# Blackfoot.net
KiCad netlist of a schematic drawn in EAGLE
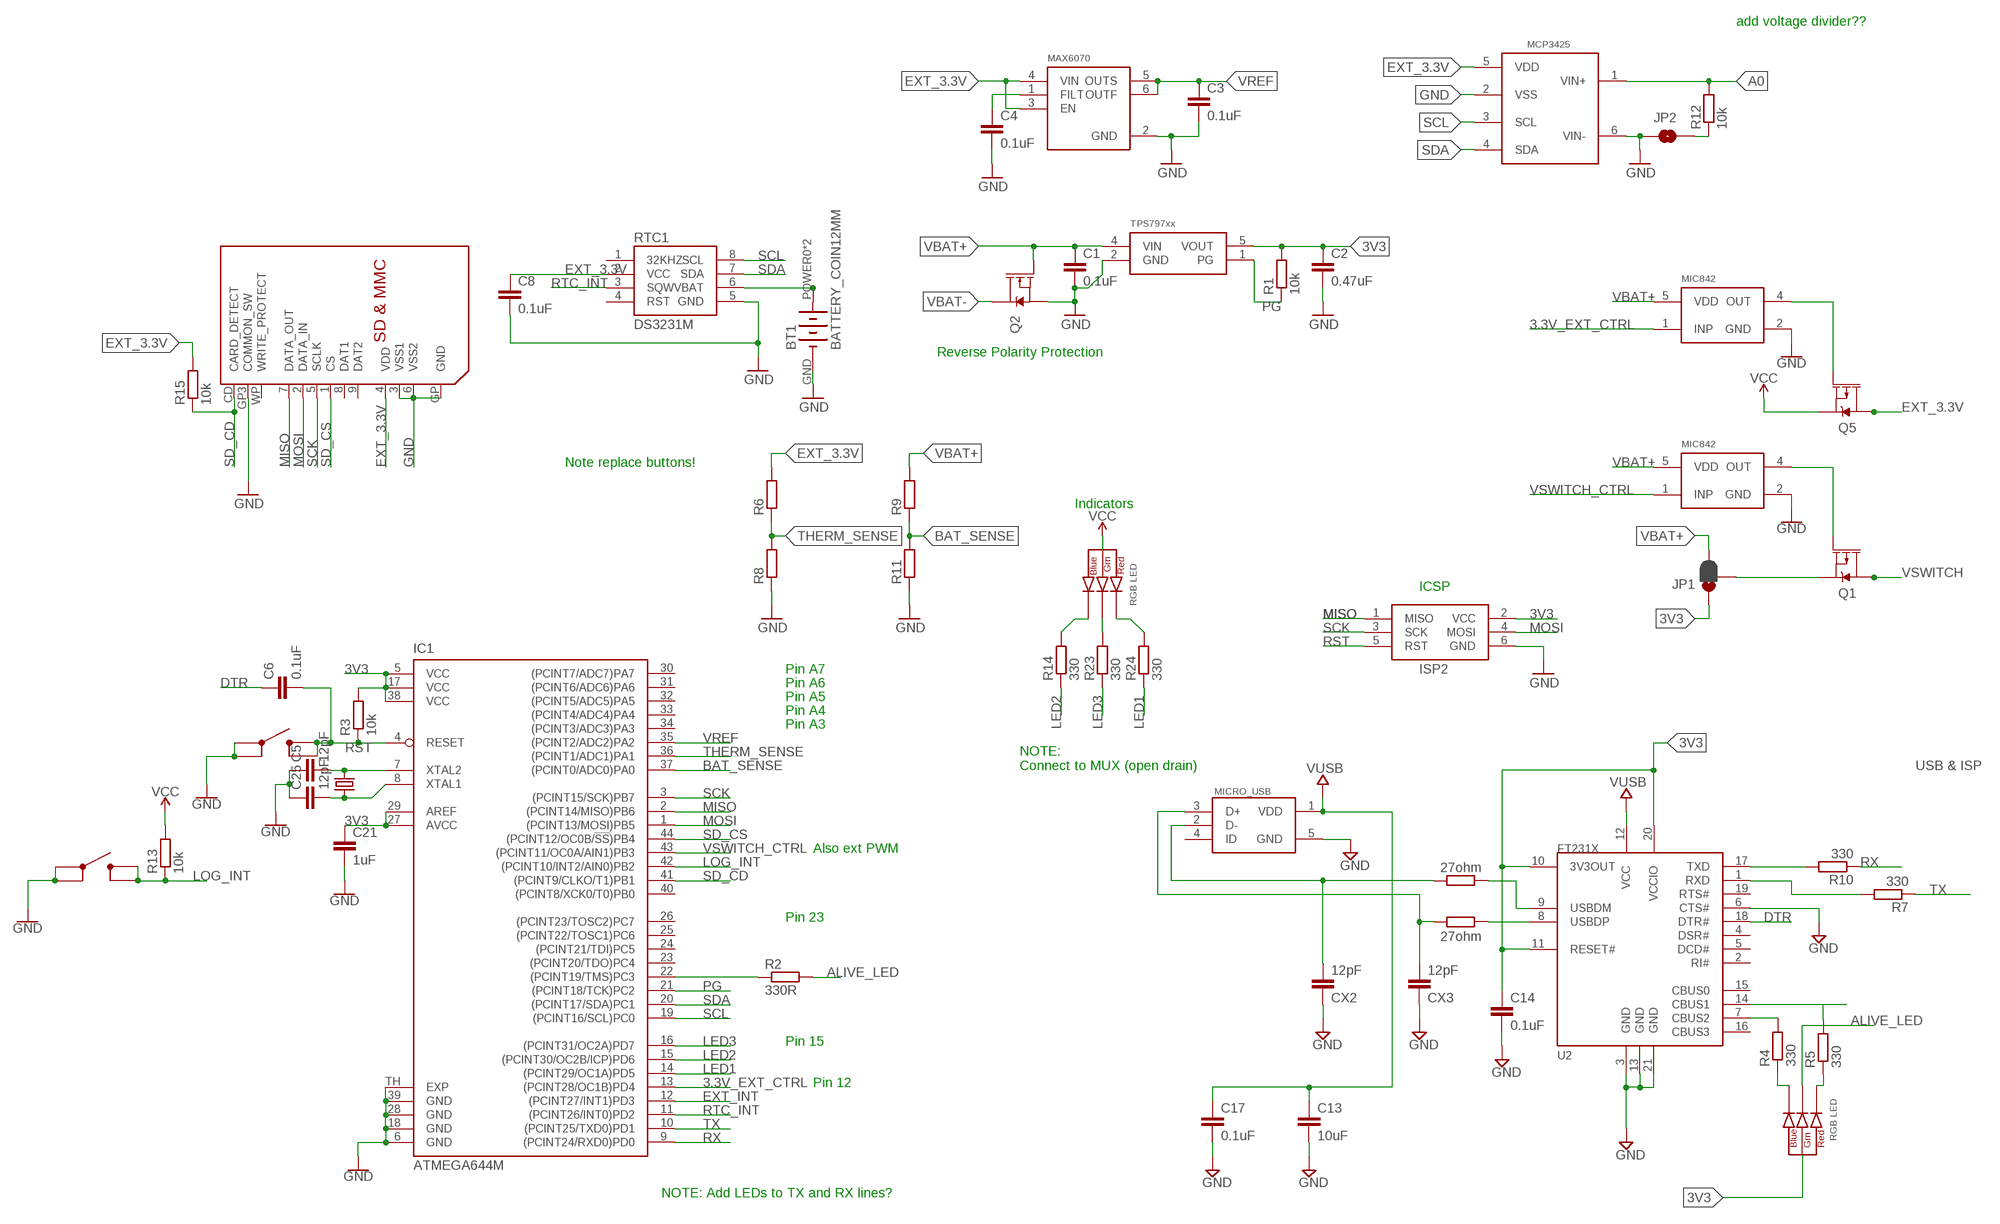
[diagram p0: schematic, sheet 1]
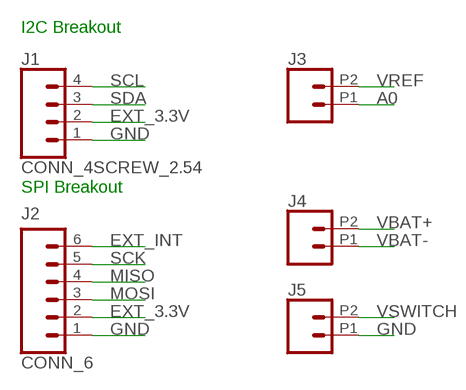
[diagram p1: schematic, sheet 2]

(export (version "E")
  (design (tool "Eeschema 10.0.6"))
  (components
    (comp (ref "J1")
      (value "CONN_4SCREW_2.54")
      (footprint "eagle-import:1X04")
      (libsource (lib "eagle-import") (part "CONN_4SCREW_2.54"))
    )
    (comp (ref "J2")
      (value "CONN_6")
      (footprint "eagle-import:1X06_SCREW")
      (libsource (lib "eagle-import") (part "CONN_6"))
    )
    (comp (ref "J3")
      (value "CONN_022.54MM_SCREWTERM")
      (footprint "eagle-import:1X02_2.54_SCREWTERM")
      (libsource (lib "eagle-import") (part "CONN_022.54MM_SCREWTERM"))
    )
    (comp (ref "J4")
      (value "CONN_022.54MM_SCREWTERM")
      (footprint "eagle-import:1X02_2.54_SCREWTERM")
      (libsource (lib "eagle-import") (part "CONN_022.54MM_SCREWTERM"))
    )
    (comp (ref "J5")
      (value "CONN_022.54MM_SCREWTERM")
      (footprint "eagle-import:1X02_2.54_SCREWTERM")
      (libsource (lib "eagle-import") (part "CONN_022.54MM_SCREWTERM"))
    )
    (comp (ref "BT1")
      (value "BATTERY_COIN12MM")
      (footprint "eagle-import:AWICKERT_LINX_BAT-HLD-012-SMT")
      (fields (field (name "MF") "Linx") (field (name "MPN") "BAT-HLD-012-SMT"))
      (libsource (lib "eagle-import") (part "BATTERY_COIN12MM"))
    )
    (comp (ref "C1")
      (value "0.1uF")
      (footprint "eagle-import:C0603")
      (libsource (lib "eagle-import") (part "bschulz_passives_C-EUC0603"))
    )
    (comp (ref "C2")
      (value "0.47uF")
      (footprint "eagle-import:C0603")
      (libsource (lib "eagle-import") (part "bschulz_passives_C-EUC0603"))
    )
    (comp (ref "C3")
      (value "0.1uF")
      (footprint "eagle-import:C0603")
      (libsource (lib "eagle-import") (part "bschulz_passives_C-EUC0603"))
    )
    (comp (ref "C4")
      (value "0.1uF")
      (footprint "eagle-import:C0603")
      (libsource (lib "eagle-import") (part "bschulz_passives_C-EUC0603"))
    )
    (comp (ref "C5")
      (value "12pF")
      (footprint "eagle-import:C0603")
      (fields
        (field (name "MF") "Samsung")
        (field (name "MPN") "CL10C120JB8NNNC")
        (field (name "DIGIKEY") "1276-1254-1-ND")
        (field (name "MF_1") "Samsung")
        (field (name "MPN_1") "CL10C120JB8NNNC")
      )
      (libsource (lib "eagle-import") (part "C-EUC060312PF"))
    )
    (comp (ref "C6")
      (value "0.1uF")
      (footprint "eagle-import:C0603")
      (fields (field (name "MF") "Samsung") (field (name "MPN") "CL10B104KO8NNNC"))
      (libsource (lib "eagle-import") (part "C-EUC06030.1UF"))
    )
    (comp (ref "C8")
      (value "0.1uF")
      (footprint "eagle-import:C0603")
      (libsource (lib "eagle-import") (part "C-EUC0603"))
    )
    (comp (ref "C13")
      (value "10uF")
      (footprint "eagle-import:C0805")
      (fields (field (name "MF") "Samsung") (field (name "MPN") "CL21A106KQCLRNC"))
      (libsource (lib "eagle-import") (part "C-EUC080510UF"))
    )
    (comp (ref "C14")
      (value "0.1uF")
      (footprint "eagle-import:C0603")
      (fields (field (name "MF") "Samsung") (field (name "MPN") "CL10B104KO8NNNC"))
      (libsource (lib "eagle-import") (part "C-EUC06030.1UF"))
    )
    (comp (ref "C17")
      (value "0.1uF")
      (footprint "eagle-import:C0603")
      (fields (field (name "MF") "Samsung") (field (name "MPN") "CL10B104KO8NNNC"))
      (libsource (lib "eagle-import") (part "C-EUC06030.1UF"))
    )
    (comp (ref "C21")
      (value "1uF")
      (footprint "eagle-import:C0603")
      (fields
        (field (name "MF") "Samsung")
        (field (name "MPN") "1276-6524-1-ND")
        (field (name "DIGIKEY") "1276-6524-1-ND")
        (field (name "MF_1") "Samsung")
        (field (name "MPN_1") "CL10B105MO8NNWC")
      )
      (libsource (lib "eagle-import") (part "C-EUC06031UF"))
    )
    (comp (ref "C25")
      (value "12pF")
      (footprint "eagle-import:C0603")
      (fields
        (field (name "MF") "Samsung")
        (field (name "MPN") "CL10C120JB8NNNC")
        (field (name "DIGIKEY") "1276-1254-1-ND")
        (field (name "MF_1") "Samsung")
        (field (name "MPN_1") "CL10C120JB8NNNC")
      )
      (libsource (lib "eagle-import") (part "C-EUC060312PF"))
    )
    (comp (ref "CX2")
      (value "12pF")
      (footprint "eagle-import:C0603")
      (fields (field (name "MF") "Samsung") (field (name "MPN") "CL10C120JB8NNNC"))
      (libsource (lib "eagle-import") (part "C-EUC060312PF"))
    )
    (comp (ref "CX3")
      (value "12pF")
      (footprint "eagle-import:C0603")
      (fields (field (name "MF") "Samsung") (field (name "MPN") "CL10C120JB8NNNC"))
      (libsource (lib "eagle-import") (part "C-EUC060312PF"))
    )
    (comp (ref "D+")
      (value "27ohm")
      (footprint "eagle-import:R0603")
      (fields
        (field (name "MF") "Yageo")
        (field (name "MPN") "RC0603FR-0727RL")
        (field (name "VALUE_PART") "27")
      )
      (libsource (lib "eagle-import") (part "R-EU_R060327"))
    )
    (comp (ref "D-")
      (value "27ohm")
      (footprint "eagle-import:R0603")
      (fields
        (field (name "MF") "Yageo")
        (field (name "MPN") "RC0603FR-0727RL")
        (field (name "VALUE_PART") "27")
      )
      (libsource (lib "eagle-import") (part "R-EU_R060327"))
    )
    (comp (ref "IC1")
      (value "ATMEGA644M")
      (footprint "eagle-import:MLF44-TH")
      (fields (field (name "MF") "Atmel") (field (name "MPN") "ATMEGA644PA-MUR"))
      (libsource (lib "eagle-import") (part "ATMEGA644M"))
    )
    (comp (ref "ISP2")
      (value "AVRISP-6")
      (footprint "eagle-import:AVRISP")
      (fields (field (name "MF") "Amphenol") (field (name "MPN") "67997-206HLF"))
      (libsource (lib "eagle-import") (part "AVRISP-6"))
    )
    (comp (ref "JP1")
      (value "JUMPER-SMT_3_1-NC_PASTE_SILK")
      (footprint "eagle-import:SMT-JUMPER_3_1-NC_PASTE_SILK")
      (libsource (lib "eagle-import") (part "JUMPER-SMT_3_1-NC_PASTE_SILK"))
    )
    (comp (ref "JP2")
      (value "JUMPER-SMT_2_NO_SILK")
      (footprint "eagle-import:SMT-JUMPER_2_NO_SILK")
      (libsource (lib "eagle-import") (part "JUMPER-SMT_2_NO_SILK"))
    )
    (comp (ref "MICRO_USB")
      (value "MICRO_USB_LONGPADS")
      (footprint "eagle-import:10118194-0001LF_10118194-0001LF_LONGER_PADS")
      (libsource (lib "eagle-import") (part "MICRO_USB_LONGPADS"))
    )
    (comp (ref "Q1")
      (value "MOSFET_PCH-IRLML2244")
      (footprint "eagle-import:SOT23-3")
      (fields (field (name "MF") "Fairchild") (field (name "MPN") "FDN360P"))
      (libsource (lib "eagle-import") (part "MOSFET_PCH-IRLML2244"))
    )
    (comp (ref "Q2")
      (value "MOSFET-NCH-DMG3404L")
      (footprint "eagle-import:SOT23-3")
      (libsource (lib "eagle-import") (part "MOSFET-NCH-DMG3404L"))
    )
    (comp (ref "Q5")
      (value "MOSFET_PCH-IRLML2244")
      (footprint "eagle-import:SOT23-3")
      (fields (field (name "MF") "Fairchild") (field (name "MPN") "FDN360P"))
      (libsource (lib "eagle-import") (part "MOSFET_PCH-IRLML2244"))
    )
    (comp (ref "R1")
      (value "10k")
      (footprint "eagle-import:R0603")
      (libsource (lib "eagle-import") (part "R-EU_R0603"))
    )
    (comp (ref "R2")
      (value "330R")
      (footprint "eagle-import:R0603")
      (libsource (lib "eagle-import") (part "R-EU_R0603"))
    )
    (comp (ref "R3")
      (value "10k")
      (footprint "eagle-import:R0603")
      (fields
        (field (name "MF") "Yageo")
        (field (name "MPN") "RC0603FR-0710KL")
        (field (name "DIGIKEY") "311-10.0KHRCT-ND")
      )
      (libsource (lib "eagle-import") (part "R-EU_R060310K"))
    )
    (comp (ref "R4")
      (value "330")
      (footprint "eagle-import:R0603")
      (fields
        (field (name "MF") "Yageo")
        (field (name "MPN") "RC0603FR-07330RL")
        (field (name "MPN_1") "RC0603FR-07330RL")
      )
      (libsource (lib "eagle-import") (part "R-EU_R0603330"))
    )
    (comp (ref "R5")
      (value "330")
      (footprint "eagle-import:R0603")
      (fields
        (field (name "MF") "Yageo")
        (field (name "MPN") "RC0603FR-07330RL")
        (field (name "DIGIKEY") "311-330HRCT-ND")
        (field (name "MF_1") "Yageo")
        (field (name "MPN_1") "RC0603FR-07330RL")
      )
      (libsource (lib "eagle-import") (part "R-EU_R0603330"))
    )
    (comp (ref "R6")
      (value "R-EU_R0603")
      (footprint "eagle-import:R0603")
      (libsource (lib "eagle-import") (part "R-EU_R0603"))
    )
    (comp (ref "R7")
      (value "330")
      (footprint "eagle-import:R0603")
      (fields
        (field (name "MF") "Yageo")
        (field (name "MPN") "RC0603FR-07330RL")
        (field (name "MPN_1") "RC0603FR-07330RL")
      )
      (libsource (lib "eagle-import") (part "R-EU_R0603330"))
    )
    (comp (ref "R8")
      (value "R-EU_R0603")
      (footprint "eagle-import:R0603")
      (libsource (lib "eagle-import") (part "R-EU_R0603"))
    )
    (comp (ref "R9")
      (value "R-EU_R0603")
      (footprint "eagle-import:R0603")
      (libsource (lib "eagle-import") (part "R-EU_R0603"))
    )
    (comp (ref "R10")
      (value "330")
      (footprint "eagle-import:R0603")
      (fields
        (field (name "MF") "Yageo")
        (field (name "MPN") "RC0603FR-07330RL")
        (field (name "MPN_1") "RC0603FR-07330RL")
      )
      (libsource (lib "eagle-import") (part "R-EU_R0603330"))
    )
    (comp (ref "R11")
      (value "R-EU_R0603")
      (footprint "eagle-import:R0603")
      (libsource (lib "eagle-import") (part "R-EU_R0603"))
    )
    (comp (ref "R12")
      (value "10k")
      (footprint "eagle-import:R0603")
      (libsource (lib "eagle-import") (part "R-EU_R0603"))
    )
    (comp (ref "R13")
      (value "10k")
      (footprint "eagle-import:R0603")
      (fields
        (field (name "MF") "Yageo")
        (field (name "MPN") "RC0603FR-0710KL")
        (field (name "DIGIKEY") "311-10.0KHRCT-ND")
      )
      (libsource (lib "eagle-import") (part "R-EU_R060310K"))
    )
    (comp (ref "R14")
      (value "330")
      (footprint "eagle-import:R0603")
      (fields
        (field (name "MF") "Yageo")
        (field (name "MPN") "RC0603FR-07330RL")
        (field (name "MPN_1") "RC0603FR-07330RL")
      )
      (libsource (lib "eagle-import") (part "R-EU_R0603330"))
    )
    (comp (ref "R15")
      (value "10k")
      (footprint "eagle-import:R0603")
      (libsource (lib "eagle-import") (part "R-EU_R0603"))
    )
    (comp (ref "R23")
      (value "330")
      (footprint "eagle-import:R0603")
      (fields
        (field (name "MF") "Yageo")
        (field (name "MPN") "RC0603FR-07330RL")
        (field (name "MPN_1") "RC0603FR-07330RL")
      )
      (libsource (lib "eagle-import") (part "R-EU_R0603330"))
    )
    (comp (ref "R24")
      (value "330")
      (footprint "eagle-import:R0603")
      (fields
        (field (name "MF") "Yageo")
        (field (name "MPN") "RC0603FR-07330RL")
        (field (name "MPN_1") "RC0603FR-07330RL")
      )
      (libsource (lib "eagle-import") (part "R-EU_R0603330"))
    )
    (comp (ref "RTC1")
      (value "DS3231M")
      (footprint "eagle-import:SO08")
      (fields (field (name "MF") "Maxim") (field (name "MPN") "DS3231MZ+"))
      (libsource (lib "eagle-import") (part "DS3231M"))
    )
    (comp (ref "U$1")
      (value "CRYSTAL_5X3.2_2LEAD")
      (footprint "eagle-import:CRYSTAL_5X3.2_2-SMD")
      (libsource (lib "eagle-import") (part "CRYSTAL_5X3.2_2LEAD"))
    )
    (comp (ref "U$3")
      (value "SDMMC06132")
      (footprint "eagle-import:06132")
      (libsource (lib "eagle-import") (part "SDMMC06132"))
    )
    (comp (ref "U$4")
      (value "MIC842")
      (footprint "eagle-import:DCK_R-PDSO-G5")
      (libsource (lib "eagle-import") (part "MIC842"))
    )
    (comp (ref "U$5")
      (value "BUTTON4.2X3.2")
      (footprint "eagle-import:SWITCH_4.2X3.2")
      (libsource (lib "eagle-import") (part "BUTTON4.2X3.2"))
    )
    (comp (ref "U$6")
      (value "TPS79733")
      (footprint "eagle-import:DCK_R-PDSO-G5")
      (fields (field (name "MF") "TI") (field (name "MPN") "TPS79733DCKR"))
      (libsource (lib "eagle-import") (part "TPS79733"))
    )
    (comp (ref "U$7")
      (value "MAX6070AAUT18")
      (footprint "eagle-import:SOT23-6L")
      (fields (field (name "MF") "Maxim") (field (name "MPN") "MAX6070BAUT18+T"))
      (libsource (lib "eagle-import") (part "MAX6070AAUT18"))
    )
    (comp (ref "U$8")
      (value "MCP3425")
      (footprint "eagle-import:SOT23-6L")
      (fields (field (name "MF") "Microchip") (field (name "MPN") "MCP3425A0T-E/CH"))
      (libsource (lib "eagle-import") (part "MCP3425"))
    )
    (comp (ref "U$9")
      (value "BUTTON4.2X3.2")
      (footprint "eagle-import:SWITCH_4.2X3.2")
      (libsource (lib "eagle-import") (part "BUTTON4.2X3.2"))
    )
    (comp (ref "U$15")
      (value "CLVBA-FKA")
      (footprint "eagle-import:CLVBA-FKA")
      (fields (field (name "MF") "Cree") (field (name "MPN") "CLVBA-FKA-CAEDH8BBB7A363"))
      (libsource (lib "eagle-import") (part "CLVBA-FKA"))
    )
    (comp (ref "U$16")
      (value "CLVBA-FKA")
      (footprint "eagle-import:CLVBA-FKA")
      (fields (field (name "MF") "Cree") (field (name "MPN") "CLVBA-FKA-CAEDH8BBB7A363"))
      (libsource (lib "eagle-import") (part "CLVBA-FKA"))
    )
    (comp (ref "U$18")
      (value "MIC842")
      (footprint "eagle-import:DCK_R-PDSO-G5")
      (libsource (lib "eagle-import") (part "MIC842"))
    )
    (comp (ref "U2")
      (value "FT231X-Q")
      (footprint "eagle-import:QFN20")
      (fields (field (name "MF") "FTDI") (field (name "MPN") "FT231XQ-R"))
      (libsource (lib "eagle-import") (part "FT231X-Q"))
    )
  )
  (nets
    (net (code "1") (name "3.3V_EXT_CTRL") (class "Default")
      (node (ref "IC1") (pin "13") (pinfunction "(PCINT28/OC1B)PD4_13") (pintype "bidirectional"))
      (node (ref "U$18") (pin "1") (pinfunction "INP_1") (pintype "input"))
    )
    (net (code "2") (name "3V3") (class "Default")
      (node (ref "C14") (pin "1") (pinfunction "1_1") (pintype "passive"))
      (node (ref "C2") (pin "1") (pinfunction "1_1") (pintype "passive"))
      (node (ref "C21") (pin "1") (pinfunction "1_1") (pintype "passive"))
      (node (ref "IC1") (pin "17") (pinfunction "VCC_17") (pintype "power_in"))
      (node (ref "IC1") (pin "27") (pinfunction "AVCC_27") (pintype "power_in"))
      (node (ref "IC1") (pin "29") (pinfunction "AREF_29") (pintype "passive"))
      (node (ref "IC1") (pin "38") (pinfunction "VCC_38") (pintype "power_in"))
      (node (ref "IC1") (pin "5") (pinfunction "VCC_5") (pintype "power_in"))
      (node (ref "ISP2") (pin "2") (pinfunction "VCC_2") (pintype "power_in"))
      (node (ref "JP1") (pin "1") (pinfunction "1_1") (pintype "passive"))
      (node (ref "Q5") (pin "2") (pinfunction "S_2") (pintype "bidirectional"))
      (node (ref "R1") (pin "2") (pinfunction "2_2") (pintype "passive"))
      (node (ref "R13") (pin "2") (pinfunction "2_2") (pintype "passive"))
      (node (ref "R3") (pin "2") (pinfunction "2_2") (pintype "passive"))
      (node (ref "U$15") (pin "2") (pinfunction "ANODE_2") (pintype "bidirectional"))
      (node (ref "U$16") (pin "2") (pinfunction "ANODE_2") (pintype "bidirectional"))
      (node (ref "U$6") (pin "5") (pinfunction "VOUT_5") (pintype "bidirectional"))
      (node (ref "U2") (pin "10") (pinfunction "3V3OUT_10") (pintype "bidirectional"))
      (node (ref "U2") (pin "11") (pinfunction "RESET#_11") (pintype "bidirectional"))
      (node (ref "U2") (pin "20") (pinfunction "VCCIO_20") (pintype "bidirectional"))
    )
    (net (code "3") (name "A0") (class "Default")
      (node (ref "J3") (pin "P1") (pinfunction "1_P1") (pintype "passive"))
      (node (ref "R12") (pin "2") (pinfunction "2_2") (pintype "passive"))
      (node (ref "U$8") (pin "1") (pinfunction "VIN+_1") (pintype "input"))
    )
    (net (code "4") (name "ALIVE_LED") (class "Default")
      (node (ref "R2") (pin "2") (pinfunction "2_2") (pintype "passive"))
      (node (ref "U$16") (pin "4") (pinfunction "GREEN_CATH_4") (pintype "bidirectional"))
    )
    (net (code "5") (name "BAT_SENSE") (class "Default")
      (node (ref "IC1") (pin "37") (pinfunction "(PCINT0/ADC0)PA0_37") (pintype "bidirectional"))
      (node (ref "R11") (pin "2") (pinfunction "2_2") (pintype "passive"))
      (node (ref "R9") (pin "1") (pinfunction "1_1") (pintype "passive"))
    )
    (net (code "6") (name "DTR") (class "Default")
      (node (ref "C6") (pin "1") (pinfunction "1_1") (pintype "passive"))
      (node (ref "U2") (pin "18") (pinfunction "DTR#_18") (pintype "bidirectional"))
    )
    (net (code "7") (name "EXT_3.3V") (class "Default")
      (node (ref "C8") (pin "1") (pinfunction "1_1") (pintype "passive"))
      (node (ref "J1") (pin "2") (pinfunction "2_2") (pintype "passive"))
      (node (ref "J2") (pin "2") (pinfunction "2_2") (pintype "passive"))
      (node (ref "Q5") (pin "3") (pinfunction "D_3") (pintype "bidirectional"))
      (node (ref "R15") (pin "2") (pinfunction "2_2") (pintype "passive"))
      (node (ref "R6") (pin "2") (pinfunction "2_2") (pintype "passive"))
      (node (ref "RTC1") (pin "2") (pinfunction "VCC_2") (pintype "power_in"))
      (node (ref "U$3") (pin "4") (pinfunction "VDD_4") (pintype "power_in"))
      (node (ref "U$7") (pin "3") (pinfunction "EN_3") (pintype "bidirectional"))
      (node (ref "U$7") (pin "4") (pinfunction "VIN_4") (pintype "bidirectional"))
      (node (ref "U$8") (pin "5") (pinfunction "VDD_5") (pintype "passive"))
    )
    (net (code "8") (name "EXT_INT") (class "Default")
      (node (ref "IC1") (pin "12") (pinfunction "(PCINT27/INT1)PD3_12") (pintype "bidirectional"))
      (node (ref "J2") (pin "6") (pinfunction "6_6") (pintype "passive"))
    )
    (net (code "9") (name "GND") (class "Default")
      (node (ref "BT1") (pin "GND") (pinfunction "-_GND") (pintype "passive"))
      (node (ref "C1") (pin "2") (pinfunction "2_2") (pintype "passive"))
      (node (ref "C13") (pin "2") (pinfunction "2_2") (pintype "passive"))
      (node (ref "C14") (pin "2") (pinfunction "2_2") (pintype "passive"))
      (node (ref "C17") (pin "2") (pinfunction "2_2") (pintype "passive"))
      (node (ref "C2") (pin "2") (pinfunction "2_2") (pintype "passive"))
      (node (ref "C21") (pin "2") (pinfunction "2_2") (pintype "passive"))
      (node (ref "C25") (pin "1") (pinfunction "1_1") (pintype "passive"))
      (node (ref "C3") (pin "2") (pinfunction "2_2") (pintype "passive"))
      (node (ref "C4") (pin "2") (pinfunction "2_2") (pintype "passive"))
      (node (ref "C5") (pin "1") (pinfunction "1_1") (pintype "passive"))
      (node (ref "C8") (pin "2") (pinfunction "2_2") (pintype "passive"))
      (node (ref "CX2") (pin "1") (pinfunction "1_1") (pintype "passive"))
      (node (ref "CX3") (pin "1") (pinfunction "1_1") (pintype "passive"))
      (node (ref "IC1") (pin "18") (pinfunction "GND_18") (pintype "power_in"))
      (node (ref "IC1") (pin "28") (pinfunction "GND_28") (pintype "power_in"))
      (node (ref "IC1") (pin "39") (pinfunction "GND_39") (pintype "power_in"))
      (node (ref "IC1") (pin "6") (pinfunction "GND_6") (pintype "power_in"))
      (node (ref "IC1") (pin "TH") (pinfunction "EXP_TH") (pintype "power_in"))
      (node (ref "ISP2") (pin "6") (pinfunction "GND_6") (pintype "power_in"))
      (node (ref "J1") (pin "1") (pinfunction "1_1") (pintype "passive"))
      (node (ref "J2") (pin "1") (pinfunction "1_1") (pintype "passive"))
      (node (ref "J5") (pin "P1") (pinfunction "1_P1") (pintype "passive"))
      (node (ref "JP2") (pin "1") (pinfunction "1_1") (pintype "passive"))
      (node (ref "MICRO_USB") (pin "5") (pinfunction "GND_5") (pintype "power_in"))
      (node (ref "Q2") (pin "2") (pinfunction "S_2") (pintype "bidirectional"))
      (node (ref "R11") (pin "1") (pinfunction "1_1") (pintype "passive"))
      (node (ref "R8") (pin "1") (pinfunction "1_1") (pintype "passive"))
      (node (ref "RTC1") (pin "5") (pinfunction "GND_5") (pintype "power_in"))
      (node (ref "U$18") (pin "2") (pinfunction "GND_2") (pintype "power_in"))
      (node (ref "U$3") (pin "3") (pinfunction "VSS1_3") (pintype "power_in"))
      (node (ref "U$3") (pin "6") (pinfunction "VSS2_6") (pintype "power_in"))
      (node (ref "U$3") (pin "GP") (pinfunction "GND_GP") (pintype "power_in"))
      (node (ref "U$3") (pin "GP3") (pinfunction "COMMON_SW_GP3") (pintype "passive"))
      (node (ref "U$4") (pin "2") (pinfunction "GND_2") (pintype "power_in"))
      (node (ref "U$5") (pin "1") (pinfunction "1_1") (pintype "bidirectional"))
      (node (ref "U$5") (pin "2") (pinfunction "2_2") (pintype "bidirectional"))
      (node (ref "U$6") (pin "2") (pinfunction "GND_2") (pintype "bidirectional"))
      (node (ref "U$7") (pin "2") (pinfunction "GND_2") (pintype "bidirectional"))
      (node (ref "U$8") (pin "2") (pinfunction "VSS_2") (pintype "passive"))
      (node (ref "U$8") (pin "6") (pinfunction "VIN-_6") (pintype "input"))
      (node (ref "U$9") (pin "1") (pinfunction "1_1") (pintype "bidirectional"))
      (node (ref "U$9") (pin "2") (pinfunction "2_2") (pintype "bidirectional"))
      (node (ref "U2") (pin "13") (pinfunction "GND_13") (pintype "bidirectional"))
      (node (ref "U2") (pin "21") (pinfunction "GND_21") (pintype "bidirectional"))
      (node (ref "U2") (pin "3") (pinfunction "GND_3") (pintype "bidirectional"))
      (node (ref "U2") (pin "6") (pinfunction "CTS#_6") (pintype "bidirectional"))
    )
    (net (code "10") (name "LED1") (class "Default")
      (node (ref "IC1") (pin "14") (pinfunction "(PCINT29/OC1A)PD5_14") (pintype "bidirectional"))
      (node (ref "R24") (pin "1") (pinfunction "1_1") (pintype "passive"))
    )
    (net (code "11") (name "LED2") (class "Default")
      (node (ref "IC1") (pin "15") (pinfunction "(PCINT30/OC2B/ICP)PD6_15") (pintype "bidirectional"))
      (node (ref "R14") (pin "1") (pinfunction "1_1") (pintype "passive"))
    )
    (net (code "12") (name "LED3") (class "Default")
      (node (ref "IC1") (pin "16") (pinfunction "(PCINT31/OC2A)PD7_16") (pintype "bidirectional"))
      (node (ref "R23") (pin "1") (pinfunction "1_1") (pintype "passive"))
    )
    (net (code "13") (name "LOG_INT") (class "Default")
      (node (ref "IC1") (pin "42") (pinfunction "(PCINT10/INT2/AIN0)PB2_42") (pintype "bidirectional"))
      (node (ref "R13") (pin "1") (pinfunction "1_1") (pintype "passive"))
      (node (ref "U$5") (pin "3") (pinfunction "4_3") (pintype "bidirectional"))
      (node (ref "U$5") (pin "4") (pinfunction "3_4") (pintype "bidirectional"))
    )
    (net (code "14") (name "MISO") (class "Default")
      (node (ref "IC1") (pin "2") (pinfunction "(PCINT14/MISO)PB6_2") (pintype "bidirectional"))
      (node (ref "ISP2") (pin "1") (pinfunction "MISO_1") (pintype "input"))
      (node (ref "J2") (pin "4") (pinfunction "4_4") (pintype "passive"))
      (node (ref "U$3") (pin "7") (pinfunction "DATA_OUT_7") (pintype "output"))
    )
    (net (code "15") (name "MOSI") (class "Default")
      (node (ref "IC1") (pin "1") (pinfunction "(PCINT13/MOSI)PB5_1") (pintype "bidirectional"))
      (node (ref "ISP2") (pin "4") (pinfunction "MOSI_4") (pintype "output"))
      (node (ref "J2") (pin "3") (pinfunction "3_3") (pintype "passive"))
      (node (ref "U$3") (pin "2") (pinfunction "DATA_IN_2") (pintype "input"))
    )
    (net (code "16") (name "Net-(IC1-(PCINT19{slash}TMS)PC3)") (class "Default")
      (node (ref "IC1") (pin "22") (pinfunction "(PCINT19/TMS)PC3_22") (pintype "output"))
      (node (ref "R2") (pin "1") (pinfunction "1_1") (pintype "passive"))
    )
    (net (code "17") (name "Net-(IC1-XTAL1)") (class "Default")
      (node (ref "C25") (pin "2") (pinfunction "2_2") (pintype "passive"))
      (node (ref "IC1") (pin "8") (pinfunction "XTAL1_8") (pintype "bidirectional"))
      (node (ref "U$1") (pin "OSC1") (pinfunction "1_OSC1") (pintype "passive"))
    )
    (net (code "18") (name "Net-(IC1-XTAL2)") (class "Default")
      (node (ref "C5") (pin "2") (pinfunction "2_2") (pintype "passive"))
      (node (ref "IC1") (pin "7") (pinfunction "XTAL2_7") (pintype "bidirectional"))
      (node (ref "U$1") (pin "OSC2") (pinfunction "2_OSC2") (pintype "passive"))
    )
    (net (code "19") (name "Net-(JP2-Pad2)") (class "Default")
      (node (ref "JP2") (pin "2") (pinfunction "2_2") (pintype "passive"))
      (node (ref "R12") (pin "1") (pinfunction "1_1") (pintype "passive"))
    )
    (net (code "20") (name "Net-(MICRO_USB-D+)") (class "Default")
      (node (ref "CX3") (pin "2") (pinfunction "2_2") (pintype "passive"))
      (node (ref "D+") (pin "2") (pinfunction "2_2") (pintype "passive"))
      (node (ref "MICRO_USB") (pin "3") (pinfunction "D+_3") (pintype "bidirectional"))
    )
    (net (code "21") (name "Net-(MICRO_USB-D-)") (class "Default")
      (node (ref "CX2") (pin "2") (pinfunction "2_2") (pintype "passive"))
      (node (ref "D-") (pin "2") (pinfunction "2_2") (pintype "passive"))
      (node (ref "MICRO_USB") (pin "2") (pinfunction "D-_2") (pintype "bidirectional"))
    )
    (net (code "22") (name "Net-(Q1-G)") (class "Default")
      (node (ref "Q1") (pin "1") (pinfunction "G_1") (pintype "bidirectional"))
      (node (ref "U$4") (pin "4") (pinfunction "OUT_4") (pintype "output"))
    )
    (net (code "23") (name "Net-(Q1-S)") (class "Default")
      (node (ref "JP1") (pin "2") (pinfunction "2_2") (pintype "passive"))
      (node (ref "Q1") (pin "2") (pinfunction "S_2") (pintype "bidirectional"))
    )
    (net (code "24") (name "Net-(Q5-G)") (class "Default")
      (node (ref "Q5") (pin "1") (pinfunction "G_1") (pintype "bidirectional"))
      (node (ref "U$18") (pin "4") (pinfunction "OUT_4") (pintype "output"))
    )
    (net (code "25") (name "Net-(RTC1-VBAT)") (class "Default")
      (node (ref "BT1") (pin "POWER0") (pinfunction "+_POWER0") (pintype "passive"))
      (node (ref "BT1") (pin "POWER1") (pinfunction "+_POWER1") (pintype "passive"))
      (node (ref "RTC1") (pin "6") (pinfunction "VBAT_6") (pintype "power_in"))
    )
    (net (code "26") (name "Net-(U$7-FILT)") (class "Default")
      (node (ref "C4") (pin "1") (pinfunction "1_1") (pintype "passive"))
      (node (ref "U$7") (pin "1") (pinfunction "FILT_1") (pintype "bidirectional"))
    )
    (net (code "27") (name "Net-(U$15-BLUE_CATH)") (class "Default")
      (node (ref "R14") (pin "2") (pinfunction "2_2") (pintype "passive"))
      (node (ref "U$15") (pin "3") (pinfunction "BLUE_CATH_3") (pintype "bidirectional"))
    )
    (net (code "28") (name "Net-(U$15-GREEN_CATH)") (class "Default")
      (node (ref "R23") (pin "2") (pinfunction "2_2") (pintype "passive"))
      (node (ref "U$15") (pin "4") (pinfunction "GREEN_CATH_4") (pintype "bidirectional"))
    )
    (net (code "29") (name "Net-(U$15-RED_CATH)") (class "Default")
      (node (ref "R24") (pin "2") (pinfunction "2_2") (pintype "passive"))
      (node (ref "U$15") (pin "1") (pinfunction "RED_CATH_1") (pintype "bidirectional"))
    )
    (net (code "30") (name "Net-(U$16-BLUE_CATH)") (class "Default")
      (node (ref "R4") (pin "1") (pinfunction "1_1") (pintype "passive"))
      (node (ref "U$16") (pin "3") (pinfunction "BLUE_CATH_3") (pintype "bidirectional"))
    )
    (net (code "31") (name "Net-(U$16-RED_CATH)") (class "Default")
      (node (ref "R5") (pin "1") (pinfunction "1_1") (pintype "passive"))
      (node (ref "U$16") (pin "1") (pinfunction "RED_CATH_1") (pintype "bidirectional"))
    )
    (net (code "32") (name "Net-(U2-CBUS1)") (class "Default")
      (node (ref "R5") (pin "2") (pinfunction "2_2") (pintype "passive"))
      (node (ref "U2") (pin "14") (pinfunction "CBUS1_14") (pintype "bidirectional"))
    )
    (net (code "33") (name "Net-(U2-CBUS2)") (class "Default")
      (node (ref "R4") (pin "2") (pinfunction "2_2") (pintype "passive"))
      (node (ref "U2") (pin "7") (pinfunction "CBUS2_7") (pintype "bidirectional"))
    )
    (net (code "34") (name "Net-(U2-RXD)") (class "Default")
      (node (ref "R7") (pin "2") (pinfunction "2_2") (pintype "passive"))
      (node (ref "U2") (pin "1") (pinfunction "RXD_1") (pintype "bidirectional"))
    )
    (net (code "35") (name "Net-(U2-TXD)") (class "Default")
      (node (ref "R10") (pin "2") (pinfunction "2_2") (pintype "passive"))
      (node (ref "U2") (pin "17") (pinfunction "TXD_17") (pintype "bidirectional"))
    )
    (net (code "36") (name "Net-(U2-USBDM)") (class "Default")
      (node (ref "D-") (pin "1") (pinfunction "1_1") (pintype "passive"))
      (node (ref "U2") (pin "9") (pinfunction "USBDM_9") (pintype "bidirectional"))
    )
    (net (code "37") (name "Net-(U2-USBDP)") (class "Default")
      (node (ref "D+") (pin "1") (pinfunction "1_1") (pintype "passive"))
      (node (ref "U2") (pin "8") (pinfunction "USBDP_8") (pintype "bidirectional"))
    )
    (net (code "38") (name "PG") (class "Default")
      (node (ref "IC1") (pin "21") (pinfunction "(PCINT18/TCK)PC2_21") (pintype "output"))
      (node (ref "R1") (pin "1") (pinfunction "1_1") (pintype "passive"))
      (node (ref "U$6") (pin "1") (pinfunction "PG_1") (pintype "bidirectional"))
    )
    (net (code "39") (name "RST") (class "Default")
      (node (ref "C6") (pin "2") (pinfunction "2_2") (pintype "passive"))
      (node (ref "IC1") (pin "4") (pinfunction "RESET_4") (pintype "input"))
      (node (ref "ISP2") (pin "5") (pinfunction "RST_5") (pintype "output"))
      (node (ref "R3") (pin "1") (pinfunction "1_1") (pintype "passive"))
      (node (ref "U$9") (pin "3") (pinfunction "4_3") (pintype "bidirectional"))
      (node (ref "U$9") (pin "4") (pinfunction "3_4") (pintype "bidirectional"))
    )
    (net (code "40") (name "RTC_INT") (class "Default")
      (node (ref "IC1") (pin "11") (pinfunction "(PCINT26/INT0)PD2_11") (pintype "bidirectional"))
      (node (ref "RTC1") (pin "3") (pinfunction "SQW_3") (pintype "output"))
    )
    (net (code "41") (name "RX") (class "Default")
      (node (ref "IC1") (pin "9") (pinfunction "(PCINT24/RXD0)PD0_9") (pintype "bidirectional"))
      (node (ref "R10") (pin "1") (pinfunction "1_1") (pintype "passive"))
    )
    (net (code "42") (name "SCK") (class "Default")
      (node (ref "IC1") (pin "3") (pinfunction "(PCINT15/SCK)PB7_3") (pintype "bidirectional"))
      (node (ref "ISP2") (pin "3") (pinfunction "SCK_3") (pintype "output"))
      (node (ref "J2") (pin "5") (pinfunction "5_5") (pintype "passive"))
      (node (ref "U$3") (pin "5") (pinfunction "SCLK_5") (pintype "input"))
    )
    (net (code "43") (name "SCL") (class "Default")
      (node (ref "IC1") (pin "19") (pinfunction "(PCINT16/SCL)PC0_19") (pintype "output"))
      (node (ref "J1") (pin "4") (pinfunction "4_4") (pintype "passive"))
      (node (ref "RTC1") (pin "8") (pinfunction "SCL_8") (pintype "bidirectional"))
      (node (ref "U$8") (pin "3") (pinfunction "SCL_3") (pintype "bidirectional"))
    )
    (net (code "44") (name "SDA") (class "Default")
      (node (ref "IC1") (pin "20") (pinfunction "(PCINT17/SDA)PC1_20") (pintype "output"))
      (node (ref "J1") (pin "3") (pinfunction "3_3") (pintype "passive"))
      (node (ref "RTC1") (pin "7") (pinfunction "SDA_7") (pintype "bidirectional"))
      (node (ref "U$8") (pin "4") (pinfunction "SDA_4") (pintype "bidirectional"))
    )
    (net (code "45") (name "SD_CD") (class "Default")
      (node (ref "IC1") (pin "41") (pinfunction "(PCINT9/CLKO/T1)PB1_41") (pintype "bidirectional"))
      (node (ref "R15") (pin "1") (pinfunction "1_1") (pintype "passive"))
      (node (ref "U$3") (pin "CD") (pinfunction "CARD_DETECT_CD") (pintype "passive"))
    )
    (net (code "46") (name "SD_CS") (class "Default")
      (node (ref "IC1") (pin "44") (pinfunction "(PCINT12/OC0B/~{SS})PB4_44") (pintype "bidirectional"))
      (node (ref "U$3") (pin "1") (pinfunction "CS_1") (pintype "input"))
    )
    (net (code "47") (name "THERM_SENSE") (class "Default")
      (node (ref "IC1") (pin "36") (pinfunction "(PCINT1/ADC1)PA1_36") (pintype "bidirectional"))
      (node (ref "R6") (pin "1") (pinfunction "1_1") (pintype "passive"))
      (node (ref "R8") (pin "2") (pinfunction "2_2") (pintype "passive"))
    )
    (net (code "48") (name "TX") (class "Default")
      (node (ref "IC1") (pin "10") (pinfunction "(PCINT25/TXD0)PD1_10") (pintype "bidirectional"))
      (node (ref "R7") (pin "1") (pinfunction "1_1") (pintype "passive"))
    )
    (net (code "49") (name "VBAT+") (class "Default")
      (node (ref "C1") (pin "1") (pinfunction "1_1") (pintype "passive"))
      (node (ref "J4") (pin "P2") (pinfunction "2_P2") (pintype "passive"))
      (node (ref "JP1") (pin "3") (pinfunction "3_3") (pintype "passive"))
      (node (ref "Q2") (pin "1") (pinfunction "G_1") (pintype "bidirectional"))
      (node (ref "R9") (pin "2") (pinfunction "2_2") (pintype "passive"))
      (node (ref "U$18") (pin "5") (pinfunction "VDD_5") (pintype "power_in"))
      (node (ref "U$4") (pin "5") (pinfunction "VDD_5") (pintype "power_in"))
      (node (ref "U$6") (pin "4") (pinfunction "VIN_4") (pintype "bidirectional"))
    )
    (net (code "50") (name "VBAT-") (class "Default")
      (node (ref "J4") (pin "P1") (pinfunction "1_P1") (pintype "passive"))
      (node (ref "Q2") (pin "3") (pinfunction "D_3") (pintype "bidirectional"))
    )
    (net (code "51") (name "VREF") (class "Default")
      (node (ref "C3") (pin "1") (pinfunction "1_1") (pintype "passive"))
      (node (ref "IC1") (pin "35") (pinfunction "(PCINT2/ADC2)PA2_35") (pintype "bidirectional"))
      (node (ref "J3") (pin "P2") (pinfunction "2_P2") (pintype "passive"))
      (node (ref "U$7") (pin "5") (pinfunction "OUTS_5") (pintype "bidirectional"))
      (node (ref "U$7") (pin "6") (pinfunction "OUTF_6") (pintype "bidirectional"))
    )
    (net (code "52") (name "VSWITCH") (class "Default")
      (node (ref "J5") (pin "P2") (pinfunction "2_P2") (pintype "passive"))
      (node (ref "Q1") (pin "3") (pinfunction "D_3") (pintype "bidirectional"))
    )
    (net (code "53") (name "VSWITCH_CTRL") (class "Default")
      (node (ref "IC1") (pin "43") (pinfunction "(PCINT11/OC0A/AIN1)PB3_43") (pintype "bidirectional"))
      (node (ref "U$4") (pin "1") (pinfunction "INP_1") (pintype "input"))
    )
    (net (code "54") (name "VUSB") (class "Default")
      (node (ref "C13") (pin "1") (pinfunction "1_1") (pintype "passive"))
      (node (ref "C17") (pin "1") (pinfunction "1_1") (pintype "passive"))
      (node (ref "MICRO_USB") (pin "1") (pinfunction "VDD_1") (pintype "power_in"))
      (node (ref "U2") (pin "12") (pinfunction "VCC_12") (pintype "bidirectional"))
    )
    (net (code "55") (name "unconnected-(IC1-(PCINT3{slash}ADC3)PA3-Pad34)") (class "Default")
      (node (ref "IC1") (pin "34") (pinfunction "(PCINT3/ADC3)PA3_34") (pintype "bidirectional"))
    )
    (net (code "56") (name "unconnected-(IC1-(PCINT4{slash}ADC4)PA4-Pad33)") (class "Default")
      (node (ref "IC1") (pin "33") (pinfunction "(PCINT4/ADC4)PA4_33") (pintype "bidirectional"))
    )
    (net (code "57") (name "unconnected-(IC1-(PCINT5{slash}ADC5)PA5-Pad32)") (class "Default")
      (node (ref "IC1") (pin "32") (pinfunction "(PCINT5/ADC5)PA5_32") (pintype "bidirectional"))
    )
    (net (code "58") (name "unconnected-(IC1-(PCINT6{slash}ADC6)PA6-Pad31)") (class "Default")
      (node (ref "IC1") (pin "31") (pinfunction "(PCINT6/ADC6)PA6_31") (pintype "bidirectional"))
    )
    (net (code "59") (name "unconnected-(IC1-(PCINT7{slash}ADC7)PA7-Pad30)") (class "Default")
      (node (ref "IC1") (pin "30") (pinfunction "(PCINT7/ADC7)PA7_30") (pintype "bidirectional"))
    )
    (net (code "60") (name "unconnected-(IC1-(PCINT8{slash}XCK0{slash}T0)PB0-Pad40)") (class "Default")
      (node (ref "IC1") (pin "40") (pinfunction "(PCINT8/XCK0/T0)PB0_40") (pintype "bidirectional"))
    )
    (net (code "61") (name "unconnected-(IC1-(PCINT20{slash}TDO)PC4-Pad23)") (class "Default")
      (node (ref "IC1") (pin "23") (pinfunction "(PCINT20/TDO)PC4_23") (pintype "output"))
    )
    (net (code "62") (name "unconnected-(IC1-(PCINT21{slash}TDI)PC5-Pad24)") (class "Default")
      (node (ref "IC1") (pin "24") (pinfunction "(PCINT21/TDI)PC5_24") (pintype "output"))
    )
    (net (code "63") (name "unconnected-(IC1-(PCINT22{slash}TOSC1)PC6-Pad25)") (class "Default")
      (node (ref "IC1") (pin "25") (pinfunction "(PCINT22/TOSC1)PC6_25") (pintype "output"))
    )
    (net (code "64") (name "unconnected-(IC1-(PCINT23{slash}TOSC2)PC7-Pad26)") (class "Default")
      (node (ref "IC1") (pin "26") (pinfunction "(PCINT23/TOSC2)PC7_26") (pintype "output"))
    )
    (net (code "65") (name "unconnected-(MICRO_USB-ID-Pad4)") (class "Default")
      (node (ref "MICRO_USB") (pin "4") (pinfunction "ID_4") (pintype "passive"))
    )
    (net (code "66") (name "unconnected-(RTC1-32KHZ-Pad1)") (class "Default")
      (node (ref "RTC1") (pin "1") (pinfunction "32KHZ_1") (pintype "output"))
    )
    (net (code "67") (name "unconnected-(RTC1-RST-Pad4)") (class "Default")
      (node (ref "RTC1") (pin "4") (pinfunction "RST_4") (pintype "bidirectional"))
    )
    (net (code "68") (name "unconnected-(U$3-DAT1-Pad8)") (class "Default")
      (node (ref "U$3") (pin "8") (pinfunction "DAT1_8") (pintype "bidirectional"))
    )
    (net (code "69") (name "unconnected-(U$3-DAT2-Pad9)") (class "Default")
      (node (ref "U$3") (pin "9") (pinfunction "DAT2_9") (pintype "bidirectional"))
    )
    (net (code "70") (name "unconnected-(U$3-WRITE_PROTECT-PadWP)") (class "Default")
      (node (ref "U$3") (pin "WP") (pinfunction "WRITE_PROTECT_WP") (pintype "passive"))
    )
    (net (code "71") (name "unconnected-(U2-CBUS0-Pad15)") (class "Default")
      (node (ref "U2") (pin "15") (pinfunction "CBUS0_15") (pintype "bidirectional"))
    )
    (net (code "72") (name "unconnected-(U2-CBUS3-Pad16)") (class "Default")
      (node (ref "U2") (pin "16") (pinfunction "CBUS3_16") (pintype "bidirectional"))
    )
    (net (code "73") (name "unconnected-(U2-DCD#-Pad5)") (class "Default")
      (node (ref "U2") (pin "5") (pinfunction "DCD#_5") (pintype "bidirectional"))
    )
    (net (code "74") (name "unconnected-(U2-DSR#-Pad4)") (class "Default")
      (node (ref "U2") (pin "4") (pinfunction "DSR#_4") (pintype "bidirectional"))
    )
    (net (code "75") (name "unconnected-(U2-RI#-Pad2)") (class "Default")
      (node (ref "U2") (pin "2") (pinfunction "RI#_2") (pintype "bidirectional"))
    )
    (net (code "76") (name "unconnected-(U2-RTS#-Pad19)") (class "Default")
      (node (ref "U2") (pin "19") (pinfunction "RTS#_19") (pintype "bidirectional"))
    )
  )
)
